# nRF.net
KiCad netlist of a schematic drawn in EAGLE
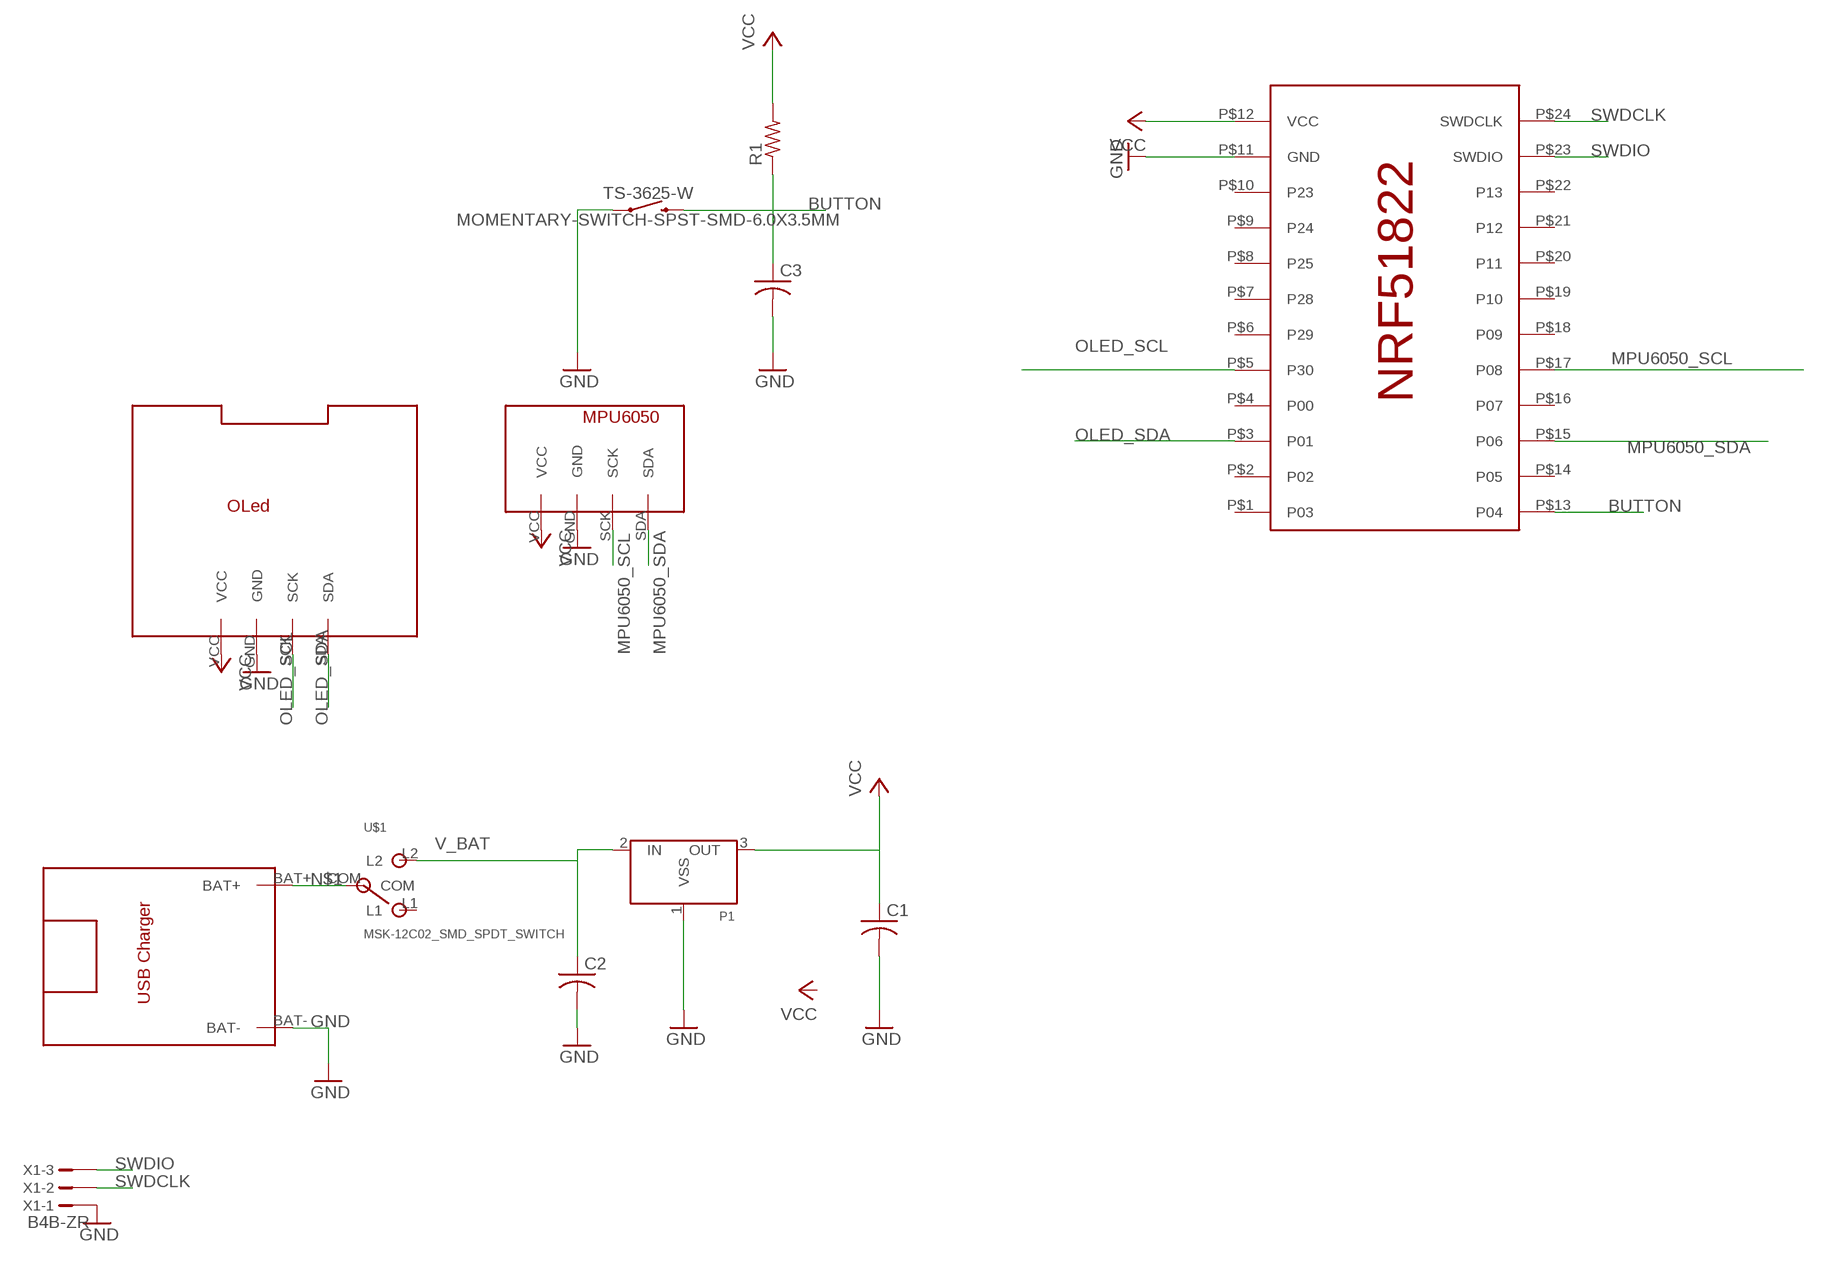
[diagram p0: schematic, sheet 1]

(export (version "E")
  (design (tool "Eeschema 10.0.6"))
  (components
    (comp (ref "C1")
      (value "C-USC0805")
      (footprint "eagle-import:C0805")
      (libsource (lib "eagle-import") (part "C-USC0805"))
    )
    (comp (ref "C2")
      (value "C-USC0805")
      (footprint "eagle-import:C0805")
      (libsource (lib "eagle-import") (part "C-USC0805"))
    )
    (comp (ref "C3")
      (value "C-USC0603")
      (footprint "eagle-import:C0603")
      (libsource (lib "eagle-import") (part "C-USC0603"))
    )
    (comp (ref "P1")
      (value "XC6206SOT-89")
      (footprint "eagle-import:SOT-89")
      (libsource (lib "eagle-import") (part "XC6206SOT-89"))
    )
    (comp (ref "R1")
      (value "R-US_R0603")
      (footprint "eagle-import:R0603")
      (libsource (lib "eagle-import") (part "R-US_R0603"))
    )
    (comp (ref "TS-3625-W")
      (value "MOMENTARY-SWITCH-SPST-SMD-6.0X3.5MM")
      (footprint "eagle-import:TACTILE_SWITCH_SMD_6.0X3.5MM")
      (libsource (lib "eagle-import") (part "MOMENTARY-SWITCH-SPST-SMD-6.0X3.5MM"))
    )
    (comp (ref "U$1")
      (value "MSK-12C02_SMD_SPDT_SWITCH")
      (footprint "eagle-import:MSK-12C02")
      (libsource (lib "eagle-import") (part "MSK-12C02_SMD_SPDT_SWITCH"))
    )
    (comp (ref "U$3")
      (value "OLED")
      (footprint "eagle-import:OLED_1.3_I2C")
      (libsource (lib "eagle-import") (part "OLED"))
    )
    (comp (ref "U$4")
      (value "MPU60XX")
      (footprint "eagle-import:MPU6050")
      (libsource (lib "eagle-import") (part "MPU60XX"))
    )
    (comp (ref "U$5")
      (value "NRF51822")
      (footprint "eagle-import:NRF51822_HSHOP")
      (libsource (lib "eagle-import") (part "NRF51822"))
    )
    (comp (ref "U$6")
      (value "TP4056")
      (footprint "eagle-import:TP4056")
      (libsource (lib "eagle-import") (part "TP4056"))
    )
    (comp (ref "X1")
      (value "B4B-ZR")
      (footprint "eagle-import:B4B-ZR")
      (fields (field (name "MF") "FARNELL") (field (name "MPN") "B4B-ZR(LF)(SN)"))
      (libsource (lib "eagle-import") (part "?4B-ZRB"))
    )
  )
  (nets
    (net (code "1") (name "/BUTTON") (class "Default")
      (node (ref "C3") (pin "1") (pinfunction "1_1") (pintype "passive"))
      (node (ref "R1") (pin "1") (pinfunction "1_1") (pintype "passive"))
      (node (ref "TS-3625-W") (pin "2") (pinfunction "2_2") (pintype "passive"))
      (node (ref "U$5") (pin "P$13") (pinfunction "P04_P$13") (pintype "bidirectional"))
    )
    (net (code "2") (name "/MPU6050_SCL") (class "Default")
      (node (ref "U$4") (pin "SCK") (pinfunction "SCK_SCK") (pintype "bidirectional"))
      (node (ref "U$5") (pin "P$17") (pinfunction "P08_P$17") (pintype "bidirectional"))
    )
    (net (code "3") (name "/MPU6050_SDA") (class "Default")
      (node (ref "U$4") (pin "SDA") (pinfunction "SDA_SDA") (pintype "bidirectional"))
      (node (ref "U$5") (pin "P$15") (pinfunction "P06_P$15") (pintype "bidirectional"))
    )
    (net (code "4") (name "/N$1") (class "Default")
      (node (ref "U$1") (pin "COM") (pinfunction "COM_COM") (pintype "bidirectional"))
      (node (ref "U$6") (pin "BAT+") (pinfunction "BAT+_BAT+") (pintype "bidirectional"))
    )
    (net (code "5") (name "/OLED_SCL") (class "Default")
      (node (ref "U$3") (pin "SCK") (pinfunction "SCK_SCK") (pintype "bidirectional"))
      (node (ref "U$5") (pin "P$5") (pinfunction "P30_P$5") (pintype "bidirectional"))
    )
    (net (code "6") (name "/OLED_SDA") (class "Default")
      (node (ref "U$3") (pin "SDA") (pinfunction "SDA_SDA") (pintype "bidirectional"))
      (node (ref "U$5") (pin "P$3") (pinfunction "P01_P$3") (pintype "bidirectional"))
    )
    (net (code "7") (name "/SWDCLK") (class "Default")
      (node (ref "U$5") (pin "P$24") (pinfunction "SWDCLK_P$24") (pintype "bidirectional"))
      (node (ref "X1") (pin "2") (pinfunction "1_2") (pintype "passive"))
    )
    (net (code "8") (name "/SWDIO") (class "Default")
      (node (ref "U$5") (pin "P$23") (pinfunction "SWDIO_P$23") (pintype "bidirectional"))
      (node (ref "X1") (pin "3") (pinfunction "1_3") (pintype "passive"))
    )
    (net (code "9") (name "/V_BAT") (class "Default")
      (node (ref "C2") (pin "1") (pinfunction "1_1") (pintype "passive"))
      (node (ref "P1") (pin "2") (pinfunction "IN_2") (pintype "bidirectional"))
      (node (ref "U$1") (pin "L2") (pinfunction "L2_L2") (pintype "bidirectional"))
    )
    (net (code "10") (name "GND") (class "Default")
      (node (ref "C1") (pin "2") (pinfunction "2_2") (pintype "passive"))
      (node (ref "C2") (pin "2") (pinfunction "2_2") (pintype "passive"))
      (node (ref "C3") (pin "2") (pinfunction "2_2") (pintype "passive"))
      (node (ref "P1") (pin "1") (pinfunction "VSS_1") (pintype "bidirectional"))
      (node (ref "TS-3625-W") (pin "1") (pinfunction "1_1") (pintype "passive"))
      (node (ref "U$3") (pin "GND") (pinfunction "GND_GND") (pintype "bidirectional"))
      (node (ref "U$4") (pin "GND") (pinfunction "GND_GND") (pintype "bidirectional"))
      (node (ref "U$5") (pin "P$11") (pinfunction "GND_P$11") (pintype "bidirectional"))
      (node (ref "U$6") (pin "BAT-") (pinfunction "BAT-_BAT-") (pintype "bidirectional"))
      (node (ref "X1") (pin "1") (pinfunction "1_1") (pintype "passive"))
    )
    (net (code "11") (name "VCC") (class "Default")
      (node (ref "C1") (pin "1") (pinfunction "1_1") (pintype "passive"))
      (node (ref "P1") (pin "3") (pinfunction "OUT_3") (pintype "bidirectional"))
      (node (ref "R1") (pin "2") (pinfunction "2_2") (pintype "passive"))
      (node (ref "U$3") (pin "VCC") (pinfunction "VCC_VCC") (pintype "bidirectional"))
      (node (ref "U$4") (pin "VCC") (pinfunction "VCC_VCC") (pintype "bidirectional"))
      (node (ref "U$5") (pin "P$12") (pinfunction "VCC_P$12") (pintype "bidirectional"))
    )
    (net (code "12") (name "unconnected-(U$1-PadL1)") (class "Default")
      (node (ref "U$1") (pin "L1") (pinfunction "L1_L1") (pintype "bidirectional"))
    )
    (net (code "13") (name "unconnected-(U$5-P00-PadP$4)") (class "Default")
      (node (ref "U$5") (pin "P$4") (pinfunction "P00_P$4") (pintype "bidirectional"))
    )
    (net (code "14") (name "unconnected-(U$5-P02-PadP$2)") (class "Default")
      (node (ref "U$5") (pin "P$2") (pinfunction "P02_P$2") (pintype "bidirectional"))
    )
    (net (code "15") (name "unconnected-(U$5-P03-PadP$1)") (class "Default")
      (node (ref "U$5") (pin "P$1") (pinfunction "P03_P$1") (pintype "bidirectional"))
    )
    (net (code "16") (name "unconnected-(U$5-P05-PadP$14)") (class "Default")
      (node (ref "U$5") (pin "P$14") (pinfunction "P05_P$14") (pintype "bidirectional"))
    )
    (net (code "17") (name "unconnected-(U$5-P07-PadP$16)") (class "Default")
      (node (ref "U$5") (pin "P$16") (pinfunction "P07_P$16") (pintype "bidirectional"))
    )
    (net (code "18") (name "unconnected-(U$5-P09-PadP$18)") (class "Default")
      (node (ref "U$5") (pin "P$18") (pinfunction "P09_P$18") (pintype "bidirectional"))
    )
    (net (code "19") (name "unconnected-(U$5-P10-PadP$19)") (class "Default")
      (node (ref "U$5") (pin "P$19") (pinfunction "P10_P$19") (pintype "bidirectional"))
    )
    (net (code "20") (name "unconnected-(U$5-P11-PadP$20)") (class "Default")
      (node (ref "U$5") (pin "P$20") (pinfunction "P11_P$20") (pintype "bidirectional"))
    )
    (net (code "21") (name "unconnected-(U$5-P12-PadP$21)") (class "Default")
      (node (ref "U$5") (pin "P$21") (pinfunction "P12_P$21") (pintype "bidirectional"))
    )
    (net (code "22") (name "unconnected-(U$5-P13-PadP$22)") (class "Default")
      (node (ref "U$5") (pin "P$22") (pinfunction "P13_P$22") (pintype "bidirectional"))
    )
    (net (code "23") (name "unconnected-(U$5-P23-PadP$10)") (class "Default")
      (node (ref "U$5") (pin "P$10") (pinfunction "P23_P$10") (pintype "bidirectional"))
    )
    (net (code "24") (name "unconnected-(U$5-P24-PadP$9)") (class "Default")
      (node (ref "U$5") (pin "P$9") (pinfunction "P24_P$9") (pintype "bidirectional"))
    )
    (net (code "25") (name "unconnected-(U$5-P25-PadP$8)") (class "Default")
      (node (ref "U$5") (pin "P$8") (pinfunction "P25_P$8") (pintype "bidirectional"))
    )
    (net (code "26") (name "unconnected-(U$5-P28-PadP$7)") (class "Default")
      (node (ref "U$5") (pin "P$7") (pinfunction "P28_P$7") (pintype "bidirectional"))
    )
    (net (code "27") (name "unconnected-(U$5-P29-PadP$6)") (class "Default")
      (node (ref "U$5") (pin "P$6") (pinfunction "P29_P$6") (pintype "bidirectional"))
    )
  )
)
